# shifter.net
KiCad netlist of a schematic drawn in Altium Designer
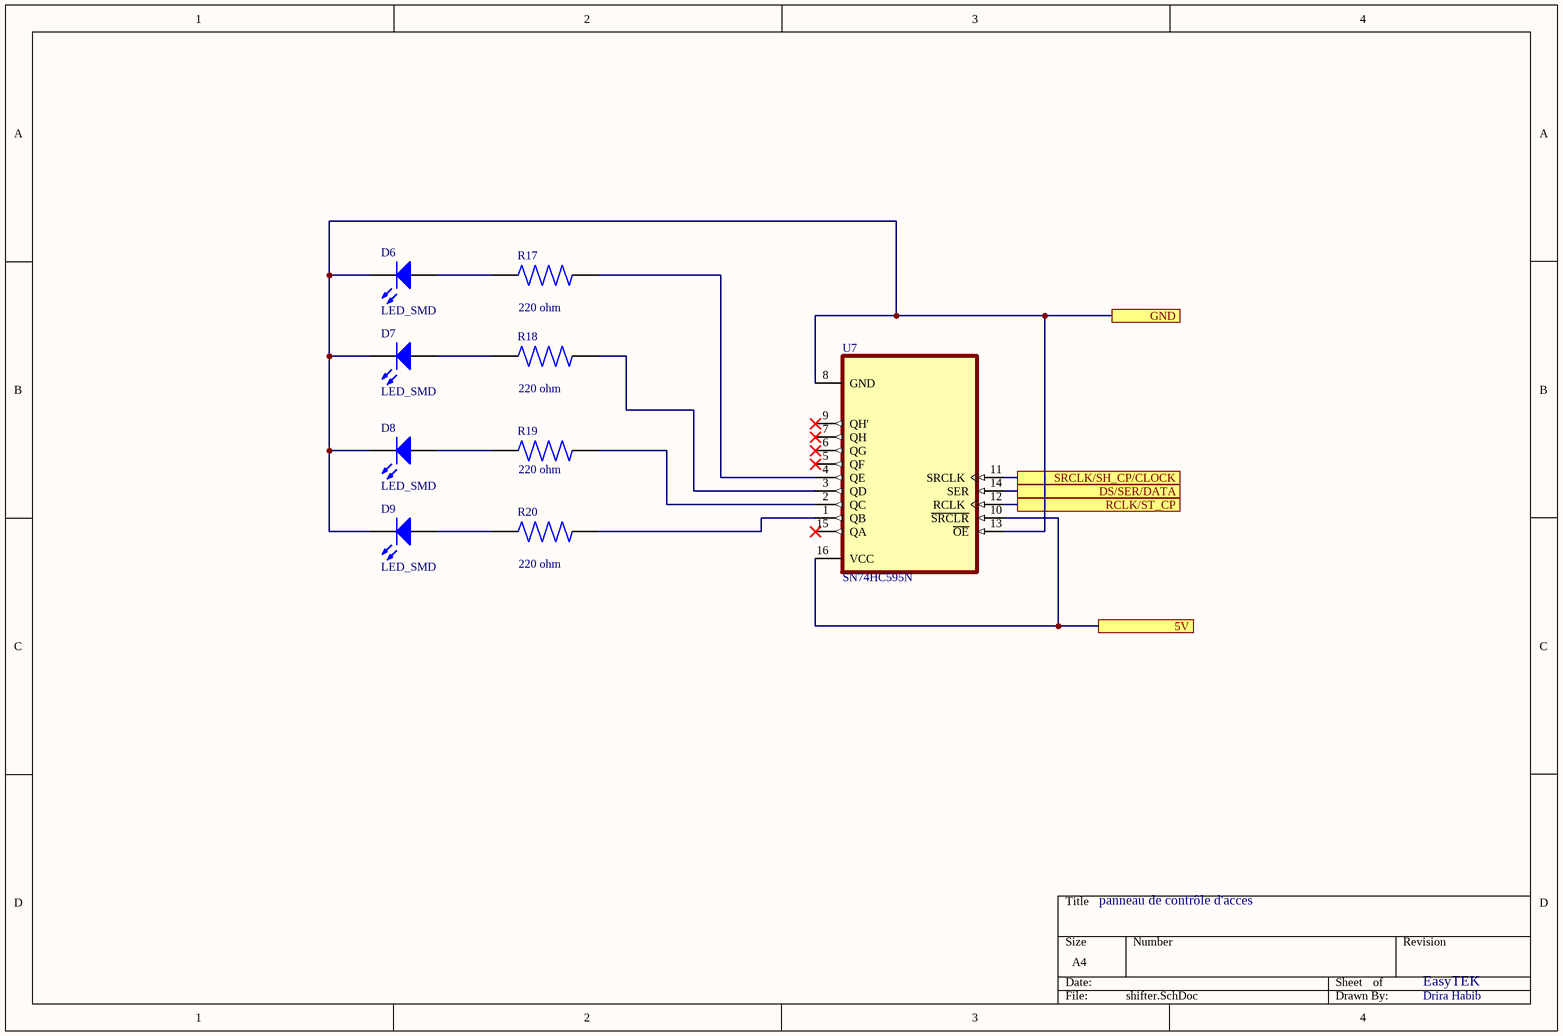
[diagram p0: shifter.SchDoc]

(export (version "E")
  (design (tool "Eeschema 10.0.6"))
  (components
    (comp (ref "D6")
      (value "LED_SMD")
      (footprint "0603_LED")
      (description "LED RED CLEAR 0603 SMD")
      (fields
        (field (name "DIGIKEY PART NUMBER") "160-1447-1-ND")
        (field (name "MANUFACTURER PART NUMBER") "LTST-C191KRKT")
      )
      (libsource (lib "Custom_Component") (part "LED_SMD"))
    )
    (comp (ref "D7")
      (value "LED_SMD")
      (footprint "0603_LED")
      (description "LED RED CLEAR 0603 SMD")
      (fields
        (field (name "DIGIKEY PART NUMBER") "160-1447-1-ND")
        (field (name "MANUFACTURER PART NUMBER") "LTST-C191KRKT")
      )
      (libsource (lib "Custom_Component") (part "LED_SMD"))
    )
    (comp (ref "D8")
      (value "LED_SMD")
      (footprint "0603_LED")
      (description "LED RED CLEAR 0603 SMD")
      (fields
        (field (name "DIGIKEY PART NUMBER") "160-1447-1-ND")
        (field (name "MANUFACTURER PART NUMBER") "LTST-C191KRKT")
      )
      (libsource (lib "Custom_Component") (part "LED_SMD"))
    )
    (comp (ref "D9")
      (value "LED_SMD")
      (footprint "0603_LED")
      (description "LED RED CLEAR 0603 SMD")
      (fields
        (field (name "DIGIKEY PART NUMBER") "160-1447-1-ND")
        (field (name "MANUFACTURER PART NUMBER") "LTST-C191KRKT")
      )
      (libsource (lib "Custom_Component") (part "LED_SMD"))
    )
    (comp (ref "R17")
      (value "220 ohm")
      (footprint "RES_ERA2APB221X")
      (fields (field (name "MP") "ERA2APB221X"))
      (libsource (lib "controlpannel") (part "ERA2APB221X"))
    )
    (comp (ref "R18")
      (value "220 ohm")
      (footprint "RES_ERA2APB221X")
      (fields (field (name "MP") "ERA2APB221X"))
      (libsource (lib "controlpannel") (part "ERA2APB221X"))
    )
    (comp (ref "R19")
      (value "220 ohm")
      (footprint "RES_ERA2APB221X")
      (fields (field (name "MP") "ERA2APB221X"))
      (libsource (lib "controlpannel") (part "ERA2APB221X"))
    )
    (comp (ref "R20")
      (value "220 ohm")
      (footprint "RES_ERA2APB221X")
      (fields (field (name "MP") "ERA2APB221X"))
      (libsource (lib "controlpannel") (part "ERA2APB221X"))
    )
    (comp (ref "U7")
      (value "SN74HC595N")
      (footprint "DIP794W45P254L1969H508Q16:DIP794W45P254L1969H508Q16")
      (libsource (lib "SN74HC595N") (part "SN74HC595N"))
    )
  )
  (nets
    (net (code "1") (name "/5V") (class "Default")
      (node (ref "U7") (pin "10") (pinfunction "~{SRCLR}_10") (pintype "input"))
      (node (ref "U7") (pin "16") (pinfunction "VCC_16") (pintype "power_in"))
    )
    (net (code "2") (name "/DS{slash}SER{slash}DATA") (class "Default")
      (node (ref "U7") (pin "14") (pinfunction "SER_14") (pintype "input"))
    )
    (net (code "3") (name "/GND") (class "Default")
      (node (ref "D6") (pin "2") (pinfunction "K_2") (pintype "passive"))
      (node (ref "D7") (pin "2") (pinfunction "K_2") (pintype "passive"))
      (node (ref "D8") (pin "2") (pinfunction "K_2") (pintype "passive"))
      (node (ref "D9") (pin "2") (pinfunction "K_2") (pintype "passive"))
      (node (ref "U7") (pin "13") (pinfunction "~{OE}_13") (pintype "input"))
      (node (ref "U7") (pin "8") (pinfunction "GND_8") (pintype "power_in"))
    )
    (net (code "4") (name "/RCLK{slash}ST_CP") (class "Default")
      (node (ref "U7") (pin "12") (pinfunction "RCLK_12") (pintype "input"))
    )
    (net (code "5") (name "/SRCLK{slash}SH_CP{slash}CLOCK") (class "Default")
      (node (ref "U7") (pin "11") (pinfunction "SRCLK_11") (pintype "input"))
    )
    (net (code "6") (name "Net-(D6-A)") (class "Default")
      (node (ref "D6") (pin "1") (pinfunction "A_1") (pintype "passive"))
      (node (ref "R17") (pin "1") (pinfunction "1_1") (pintype "passive"))
    )
    (net (code "7") (name "Net-(D7-A)") (class "Default")
      (node (ref "D7") (pin "1") (pinfunction "A_1") (pintype "passive"))
      (node (ref "R18") (pin "1") (pinfunction "1_1") (pintype "passive"))
    )
    (net (code "8") (name "Net-(D8-A)") (class "Default")
      (node (ref "D8") (pin "1") (pinfunction "A_1") (pintype "passive"))
      (node (ref "R19") (pin "1") (pinfunction "1_1") (pintype "passive"))
    )
    (net (code "9") (name "Net-(D9-A)") (class "Default")
      (node (ref "D9") (pin "1") (pinfunction "A_1") (pintype "passive"))
      (node (ref "R20") (pin "1") (pinfunction "1_1") (pintype "passive"))
    )
    (net (code "10") (name "Net-(U7-QB)") (class "Default")
      (node (ref "R20") (pin "2") (pinfunction "2_2") (pintype "passive"))
      (node (ref "U7") (pin "1") (pinfunction "QB_1") (pintype "output"))
    )
    (net (code "11") (name "Net-(U7-QC)") (class "Default")
      (node (ref "R19") (pin "2") (pinfunction "2_2") (pintype "passive"))
      (node (ref "U7") (pin "2") (pinfunction "QC_2") (pintype "output"))
    )
    (net (code "12") (name "Net-(U7-QD)") (class "Default")
      (node (ref "R18") (pin "2") (pinfunction "2_2") (pintype "passive"))
      (node (ref "U7") (pin "3") (pinfunction "QD_3") (pintype "output"))
    )
    (net (code "13") (name "Net-(U7-QE)") (class "Default")
      (node (ref "R17") (pin "2") (pinfunction "2_2") (pintype "passive"))
      (node (ref "U7") (pin "4") (pinfunction "QE_4") (pintype "output"))
    )
    (net (code "14") (name "unconnected-(U7-QA-Pad15)") (class "Default")
      (node (ref "U7") (pin "15") (pinfunction "QA_15") (pintype "output+no_connect"))
    )
    (net (code "15") (name "unconnected-(U7-QF-Pad5)") (class "Default")
      (node (ref "U7") (pin "5") (pinfunction "QF_5") (pintype "output+no_connect"))
    )
    (net (code "16") (name "unconnected-(U7-QG-Pad6)") (class "Default")
      (node (ref "U7") (pin "6") (pinfunction "QG_6") (pintype "output+no_connect"))
    )
    (net (code "17") (name "unconnected-(U7-QH'-Pad9)") (class "Default")
      (node (ref "U7") (pin "9") (pinfunction "QH'_9") (pintype "output+no_connect"))
    )
    (net (code "18") (name "unconnected-(U7-QH-Pad7)") (class "Default")
      (node (ref "U7") (pin "7") (pinfunction "QH_7") (pintype "output+no_connect"))
    )
  )
)
